# Caps.net
KiCad netlist of a schematic drawn in Altium Designer
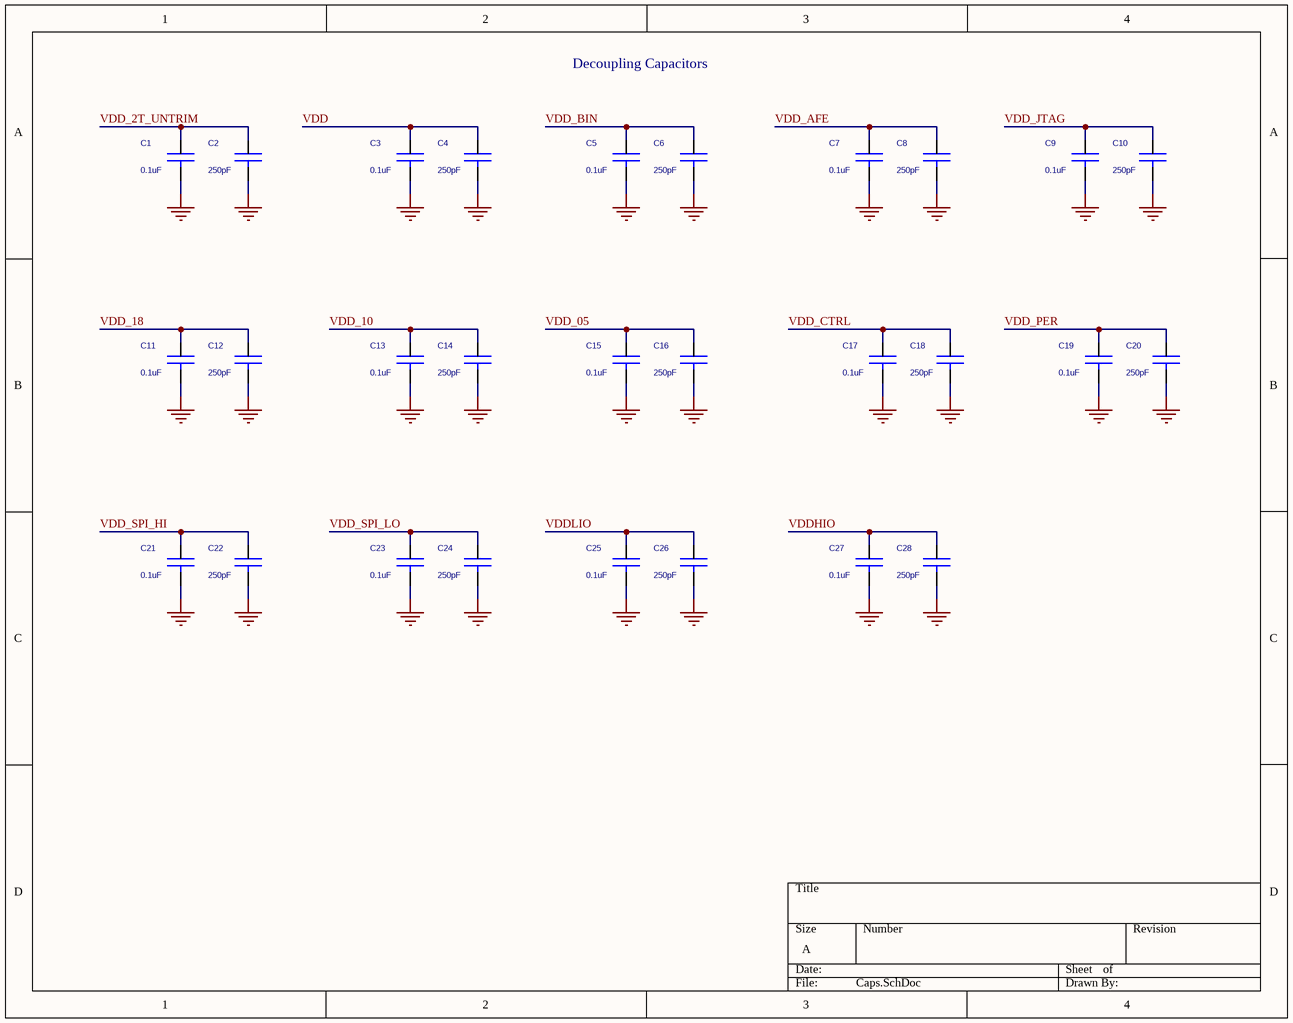
[diagram p0: Caps.SchDoc]

(export (version "E")
  (design (tool "Eeschema 10.0.6"))
  (components
    (comp (ref "C1") (value "0.1uF") (footprint "0402") (libsource (lib "*") (part "C")))
    (comp (ref "C2") (value "250pF") (footprint "0402") (libsource (lib "*") (part "C")))
    (comp (ref "C3") (value "0.1uF") (footprint "0402") (libsource (lib "*") (part "C")))
    (comp (ref "C4") (value "250pF") (footprint "0402") (libsource (lib "*") (part "C")))
    (comp (ref "C5") (value "0.1uF") (footprint "0402") (libsource (lib "*") (part "C")))
    (comp (ref "C6") (value "250pF") (footprint "0402") (libsource (lib "*") (part "C")))
    (comp (ref "C7") (value "0.1uF") (footprint "0402") (libsource (lib "*") (part "C")))
    (comp (ref "C8") (value "250pF") (footprint "0402") (libsource (lib "*") (part "C")))
    (comp (ref "C9") (value "0.1uF") (footprint "0402") (libsource (lib "*") (part "C")))
    (comp (ref "C10") (value "250pF") (footprint "0402") (libsource (lib "*") (part "C")))
    (comp (ref "C11") (value "0.1uF") (footprint "0402") (libsource (lib "*") (part "C")))
    (comp (ref "C12") (value "250pF") (footprint "0402") (libsource (lib "*") (part "C")))
    (comp (ref "C13") (value "0.1uF") (footprint "0402") (libsource (lib "*") (part "C")))
    (comp (ref "C14") (value "250pF") (footprint "0402") (libsource (lib "*") (part "C")))
    (comp (ref "C15") (value "0.1uF") (footprint "0402") (libsource (lib "*") (part "C")))
    (comp (ref "C16") (value "250pF") (footprint "0402") (libsource (lib "*") (part "C")))
    (comp (ref "C17") (value "0.1uF") (footprint "0402") (libsource (lib "*") (part "C")))
    (comp (ref "C18") (value "250pF") (footprint "0402") (libsource (lib "*") (part "C")))
    (comp (ref "C19") (value "0.1uF") (footprint "0402") (libsource (lib "*") (part "C")))
    (comp (ref "C20") (value "250pF") (footprint "0402") (libsource (lib "*") (part "C")))
    (comp (ref "C21") (value "0.1uF") (footprint "0402") (libsource (lib "*") (part "C")))
    (comp (ref "C22") (value "250pF") (footprint "0402") (libsource (lib "*") (part "C")))
    (comp (ref "C23") (value "0.1uF") (footprint "0402") (libsource (lib "*") (part "C")))
    (comp (ref "C24") (value "250pF") (footprint "0402") (libsource (lib "*") (part "C")))
    (comp (ref "C25") (value "0.1uF") (footprint "0402") (libsource (lib "*") (part "C")))
    (comp (ref "C26") (value "250pF") (footprint "0402") (libsource (lib "*") (part "C")))
    (comp (ref "C27") (value "0.1uF") (footprint "0402") (libsource (lib "*") (part "C")))
    (comp (ref "C28") (value "250pF") (footprint "0402") (libsource (lib "*") (part "C")))
  )
  (nets
    (net (code "1") (name "/VDD") (class "Default")
      (node (ref "C3") (pin "1") (pinfunction "1_1") (pintype "passive"))
      (node (ref "C4") (pin "1") (pinfunction "1_1") (pintype "passive"))
    )
    (net (code "2") (name "/VDDHIO") (class "Default")
      (node (ref "C27") (pin "1") (pinfunction "1_1") (pintype "passive"))
      (node (ref "C28") (pin "1") (pinfunction "1_1") (pintype "passive"))
    )
    (net (code "3") (name "/VDDLIO") (class "Default")
      (node (ref "C25") (pin "1") (pinfunction "1_1") (pintype "passive"))
      (node (ref "C26") (pin "1") (pinfunction "1_1") (pintype "passive"))
    )
    (net (code "4") (name "/VDD_2T_UNTRIM") (class "Default")
      (node (ref "C1") (pin "1") (pinfunction "1_1") (pintype "passive"))
      (node (ref "C2") (pin "1") (pinfunction "1_1") (pintype "passive"))
    )
    (net (code "5") (name "/VDD_05") (class "Default")
      (node (ref "C15") (pin "1") (pinfunction "1_1") (pintype "passive"))
      (node (ref "C16") (pin "1") (pinfunction "1_1") (pintype "passive"))
    )
    (net (code "6") (name "/VDD_10") (class "Default")
      (node (ref "C13") (pin "1") (pinfunction "1_1") (pintype "passive"))
      (node (ref "C14") (pin "1") (pinfunction "1_1") (pintype "passive"))
    )
    (net (code "7") (name "/VDD_18") (class "Default")
      (node (ref "C11") (pin "1") (pinfunction "1_1") (pintype "passive"))
      (node (ref "C12") (pin "1") (pinfunction "1_1") (pintype "passive"))
    )
    (net (code "8") (name "/VDD_AFE") (class "Default")
      (node (ref "C7") (pin "1") (pinfunction "1_1") (pintype "passive"))
      (node (ref "C8") (pin "1") (pinfunction "1_1") (pintype "passive"))
    )
    (net (code "9") (name "/VDD_BIN") (class "Default")
      (node (ref "C5") (pin "1") (pinfunction "1_1") (pintype "passive"))
      (node (ref "C6") (pin "1") (pinfunction "1_1") (pintype "passive"))
    )
    (net (code "10") (name "/VDD_CTRL") (class "Default")
      (node (ref "C17") (pin "1") (pinfunction "1_1") (pintype "passive"))
      (node (ref "C18") (pin "1") (pinfunction "1_1") (pintype "passive"))
    )
    (net (code "11") (name "/VDD_JTAG") (class "Default")
      (node (ref "C10") (pin "1") (pinfunction "1_1") (pintype "passive"))
      (node (ref "C9") (pin "1") (pinfunction "1_1") (pintype "passive"))
    )
    (net (code "12") (name "/VDD_PER") (class "Default")
      (node (ref "C19") (pin "1") (pinfunction "1_1") (pintype "passive"))
      (node (ref "C20") (pin "1") (pinfunction "1_1") (pintype "passive"))
    )
    (net (code "13") (name "/VDD_SPI_HI") (class "Default")
      (node (ref "C21") (pin "1") (pinfunction "1_1") (pintype "passive"))
      (node (ref "C22") (pin "1") (pinfunction "1_1") (pintype "passive"))
    )
    (net (code "14") (name "/VDD_SPI_LO") (class "Default")
      (node (ref "C23") (pin "1") (pinfunction "1_1") (pintype "passive"))
      (node (ref "C24") (pin "1") (pinfunction "1_1") (pintype "passive"))
    )
    (net (code "15") (name "GND") (class "Default")
      (node (ref "C1") (pin "2") (pinfunction "2_2") (pintype "passive"))
      (node (ref "C10") (pin "2") (pinfunction "2_2") (pintype "passive"))
      (node (ref "C11") (pin "2") (pinfunction "2_2") (pintype "passive"))
      (node (ref "C12") (pin "2") (pinfunction "2_2") (pintype "passive"))
      (node (ref "C13") (pin "2") (pinfunction "2_2") (pintype "passive"))
      (node (ref "C14") (pin "2") (pinfunction "2_2") (pintype "passive"))
      (node (ref "C15") (pin "2") (pinfunction "2_2") (pintype "passive"))
      (node (ref "C16") (pin "2") (pinfunction "2_2") (pintype "passive"))
      (node (ref "C17") (pin "2") (pinfunction "2_2") (pintype "passive"))
      (node (ref "C18") (pin "2") (pinfunction "2_2") (pintype "passive"))
      (node (ref "C19") (pin "2") (pinfunction "2_2") (pintype "passive"))
      (node (ref "C2") (pin "2") (pinfunction "2_2") (pintype "passive"))
      (node (ref "C20") (pin "2") (pinfunction "2_2") (pintype "passive"))
      (node (ref "C21") (pin "2") (pinfunction "2_2") (pintype "passive"))
      (node (ref "C22") (pin "2") (pinfunction "2_2") (pintype "passive"))
      (node (ref "C23") (pin "2") (pinfunction "2_2") (pintype "passive"))
      (node (ref "C24") (pin "2") (pinfunction "2_2") (pintype "passive"))
      (node (ref "C25") (pin "2") (pinfunction "2_2") (pintype "passive"))
      (node (ref "C26") (pin "2") (pinfunction "2_2") (pintype "passive"))
      (node (ref "C27") (pin "2") (pinfunction "2_2") (pintype "passive"))
      (node (ref "C28") (pin "2") (pinfunction "2_2") (pintype "passive"))
      (node (ref "C3") (pin "2") (pinfunction "2_2") (pintype "passive"))
      (node (ref "C4") (pin "2") (pinfunction "2_2") (pintype "passive"))
      (node (ref "C5") (pin "2") (pinfunction "2_2") (pintype "passive"))
      (node (ref "C6") (pin "2") (pinfunction "2_2") (pintype "passive"))
      (node (ref "C7") (pin "2") (pinfunction "2_2") (pintype "passive"))
      (node (ref "C8") (pin "2") (pinfunction "2_2") (pintype "passive"))
      (node (ref "C9") (pin "2") (pinfunction "2_2") (pintype "passive"))
    )
  )
)
